# nRF24L01_SMD_402.net
KiCad netlist of a schematic drawn in EAGLE
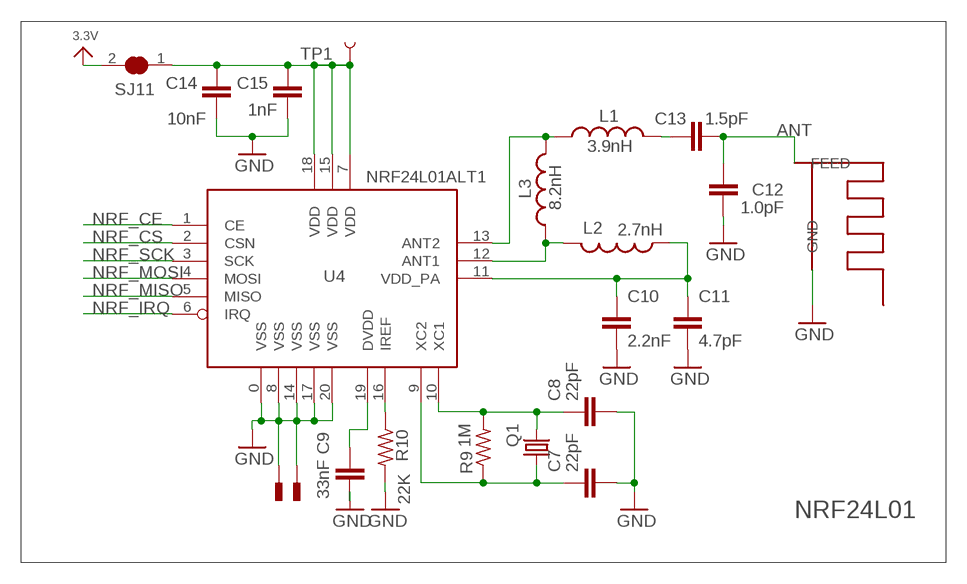
[diagram p0: schematic, sheet 1]

(export (version "E")
  (design (tool "Eeschema 10.0.6"))
  (components
    (comp (ref "ANT2")
      (value "NRF24L01_ANTENNA")
      (footprint "eagle-import:NRF24L01_ANT")
      (libsource (lib "eagle-import") (part "NRF24L01_ANTENNA"))
    )
    (comp (ref "C7")
      (value "22pF")
      (footprint "eagle-import:C0402")
      (libsource (lib "eagle-import") (part "C-EUC0402"))
    )
    (comp (ref "C8")
      (value "22pF")
      (footprint "eagle-import:C0402")
      (libsource (lib "eagle-import") (part "C-EUC0402"))
    )
    (comp (ref "C9")
      (value "33nF")
      (footprint "eagle-import:C0402")
      (libsource (lib "eagle-import") (part "C-EUC0402"))
    )
    (comp (ref "C10")
      (value "2.2nF")
      (footprint "eagle-import:C0402")
      (libsource (lib "eagle-import") (part "C-EUC0402"))
    )
    (comp (ref "C11")
      (value "4.7pF")
      (footprint "eagle-import:C0402")
      (libsource (lib "eagle-import") (part "C-EUC0402"))
    )
    (comp (ref "C12")
      (value "1.0pF")
      (footprint "eagle-import:C0402")
      (libsource (lib "eagle-import") (part "C-EUC0402"))
    )
    (comp (ref "C13")
      (value "1.5pF")
      (footprint "eagle-import:C0402")
      (libsource (lib "eagle-import") (part "C-EUC0402"))
    )
    (comp (ref "C14")
      (value "10nF")
      (footprint "eagle-import:C0402")
      (libsource (lib "eagle-import") (part "C-EUC0402"))
    )
    (comp (ref "C15")
      (value "1nF")
      (footprint "eagle-import:C0402")
      (libsource (lib "eagle-import") (part "C-EUC0402"))
    )
    (comp (ref "L1")
      (value "3.9nH")
      (footprint "eagle-import:L0402")
      (libsource (lib "eagle-import") (part "L-USL0402"))
    )
    (comp (ref "L2")
      (value "2.7nH")
      (footprint "eagle-import:L0402")
      (libsource (lib "eagle-import") (part "L-USL0402"))
    )
    (comp (ref "L3")
      (value "8.2nH")
      (footprint "eagle-import:L0402")
      (libsource (lib "eagle-import") (part "L-USL0402"))
    )
    (comp (ref "Q1")
      (value "KX-7")
      (footprint "eagle-import:3.2X2.5_KX-7")
      (libsource (lib "eagle-import") (part "KX-7"))
    )
    (comp (ref "R9")
      (value "1M")
      (footprint "eagle-import:R0402")
      (libsource (lib "eagle-import") (part "R-US_R0402"))
    )
    (comp (ref "R10")
      (value "22K")
      (footprint "eagle-import:R0402")
      (libsource (lib "eagle-import") (part "R-US_R0402"))
    )
    (comp (ref "SJ11")
      (value "SOLDERJUMPER_CLOSED")
      (footprint "eagle-import:SOLDERJUMPER_CLOSEDWIRE")
      (libsource (lib "eagle-import") (part "SOLDERJUMPER_CLOSED"))
    )
    (comp (ref "TP1")
      (value "TEST-POINT3X5")
      (footprint "eagle-import:PAD.03X.05")
      (libsource (lib "eagle-import") (part "TEST-POINT3X5"))
    )
    (comp (ref "U$27")
      (value "PAD")
      (footprint "eagle-import:PAD-0.008")
      (libsource (lib "eagle-import") (part "PAD"))
    )
    (comp (ref "U$28")
      (value "PAD")
      (footprint "eagle-import:PAD-0.008")
      (libsource (lib "eagle-import") (part "PAD"))
    )
    (comp (ref "U4")
      (value "NRF24L01ALT1")
      (footprint "eagle-import:QFN20_ALT1")
      (libsource (lib "eagle-import") (part "NRF24L01ALT1"))
    )
  )
  (nets
    (net (code "1") (name "/ANT") (class "Default")
      (node (ref "ANT2") (pin "FEED") (pinfunction "FEED_FEED") (pintype "bidirectional"))
      (node (ref "C12") (pin "2") (pinfunction "2_2") (pintype "passive"))
      (node (ref "C13") (pin "2") (pinfunction "2_2") (pintype "passive"))
    )
    (net (code "2") (name "/NRF_CE") (class "Default")
      (node (ref "U4") (pin "1") (pinfunction "CE_1") (pintype "input"))
    )
    (net (code "3") (name "/NRF_CS") (class "Default")
      (node (ref "U4") (pin "2") (pinfunction "CSN_2") (pintype "input"))
    )
    (net (code "4") (name "/NRF_IRQ") (class "Default")
      (node (ref "U4") (pin "6") (pinfunction "IRQ_6") (pintype "output"))
    )
    (net (code "5") (name "/NRF_MISO") (class "Default")
      (node (ref "U4") (pin "5") (pinfunction "MISO_5") (pintype "output"))
    )
    (net (code "6") (name "/NRF_MOSI") (class "Default")
      (node (ref "U4") (pin "4") (pinfunction "MOSI_4") (pintype "input"))
    )
    (net (code "7") (name "/NRF_SCK") (class "Default")
      (node (ref "U4") (pin "3") (pinfunction "SCK_3") (pintype "input"))
    )
    (net (code "8") (name "3.3V") (class "Default")
      (node (ref "SJ11") (pin "2") (pinfunction "2_2") (pintype "passive"))
    )
    (net (code "9") (name "GND") (class "Default")
      (node (ref "ANT2") (pin "GND") (pinfunction "GND_GND") (pintype "bidirectional"))
      (node (ref "C10") (pin "2") (pinfunction "2_2") (pintype "passive"))
      (node (ref "C11") (pin "2") (pinfunction "2_2") (pintype "passive"))
      (node (ref "C12") (pin "1") (pinfunction "1_1") (pintype "passive"))
      (node (ref "C14") (pin "1") (pinfunction "1_1") (pintype "passive"))
      (node (ref "C15") (pin "1") (pinfunction "1_1") (pintype "passive"))
      (node (ref "C7") (pin "2") (pinfunction "2_2") (pintype "passive"))
      (node (ref "C8") (pin "2") (pinfunction "2_2") (pintype "passive"))
      (node (ref "C9") (pin "2") (pinfunction "2_2") (pintype "passive"))
      (node (ref "R10") (pin "2") (pinfunction "2_2") (pintype "passive"))
      (node (ref "U$27") (pin "P$1") (pinfunction "P$1_P$1") (pintype "bidirectional"))
      (node (ref "U$28") (pin "P$1") (pinfunction "P$1_P$1") (pintype "bidirectional"))
      (node (ref "U4") (pin "0") (pinfunction "VSS_0") (pintype "power_in"))
      (node (ref "U4") (pin "14") (pinfunction "VSS_14") (pintype "power_in"))
      (node (ref "U4") (pin "17") (pinfunction "VSS_17") (pintype "power_in"))
      (node (ref "U4") (pin "20") (pinfunction "VSS_20") (pintype "power_in"))
      (node (ref "U4") (pin "8") (pinfunction "VSS_8") (pintype "power_in"))
    )
    (net (code "10") (name "Net-(C13-Pad1)") (class "Default")
      (node (ref "C13") (pin "1") (pinfunction "1_1") (pintype "passive"))
      (node (ref "L1") (pin "2") (pinfunction "2_2") (pintype "passive"))
    )
    (net (code "11") (name "Net-(Q1-2)") (class "Default")
      (node (ref "C8") (pin "1") (pinfunction "1_1") (pintype "passive"))
      (node (ref "Q1") (pin "3") (pinfunction "2_3") (pintype "passive"))
      (node (ref "R9") (pin "2") (pinfunction "2_2") (pintype "passive"))
      (node (ref "U4") (pin "10") (pinfunction "XC1_10") (pintype "input"))
    )
    (net (code "12") (name "Net-(TP1-1)") (class "Default")
      (node (ref "C14") (pin "2") (pinfunction "2_2") (pintype "passive"))
      (node (ref "C15") (pin "2") (pinfunction "2_2") (pintype "passive"))
      (node (ref "SJ11") (pin "1") (pinfunction "1_1") (pintype "passive"))
      (node (ref "TP1") (pin "P$1") (pinfunction "1_P$1") (pintype "bidirectional"))
      (node (ref "U4") (pin "15") (pinfunction "VDD_15") (pintype "power_in"))
      (node (ref "U4") (pin "18") (pinfunction "VDD_18") (pintype "power_in"))
      (node (ref "U4") (pin "7") (pinfunction "VDD_7") (pintype "power_in"))
    )
    (net (code "13") (name "Net-(U4-ANT1)") (class "Default")
      (node (ref "L2") (pin "2") (pinfunction "2_2") (pintype "passive"))
      (node (ref "L3") (pin "1") (pinfunction "1_1") (pintype "passive"))
      (node (ref "U4") (pin "12") (pinfunction "ANT1_12") (pintype "output"))
    )
    (net (code "14") (name "Net-(U4-ANT2)") (class "Default")
      (node (ref "L1") (pin "1") (pinfunction "1_1") (pintype "passive"))
      (node (ref "L3") (pin "2") (pinfunction "2_2") (pintype "passive"))
      (node (ref "U4") (pin "13") (pinfunction "ANT2_13") (pintype "output"))
    )
    (net (code "15") (name "Net-(U4-DVDD)") (class "Default")
      (node (ref "C9") (pin "1") (pinfunction "1_1") (pintype "passive"))
      (node (ref "U4") (pin "19") (pinfunction "DVDD_19") (pintype "power_in"))
    )
    (net (code "16") (name "Net-(U4-IREF)") (class "Default")
      (node (ref "R10") (pin "1") (pinfunction "1_1") (pintype "passive"))
      (node (ref "U4") (pin "16") (pinfunction "IREF_16") (pintype "input"))
    )
    (net (code "17") (name "Net-(U4-VDD_PA)") (class "Default")
      (node (ref "C10") (pin "1") (pinfunction "1_1") (pintype "passive"))
      (node (ref "C11") (pin "1") (pinfunction "1_1") (pintype "passive"))
      (node (ref "L2") (pin "1") (pinfunction "1_1") (pintype "passive"))
      (node (ref "U4") (pin "11") (pinfunction "VDD_PA_11") (pintype "power_in"))
    )
    (net (code "18") (name "Net-(U4-XC2)") (class "Default")
      (node (ref "C7") (pin "1") (pinfunction "1_1") (pintype "passive"))
      (node (ref "Q1") (pin "1") (pinfunction "1_1") (pintype "passive"))
      (node (ref "R9") (pin "1") (pinfunction "1_1") (pintype "passive"))
      (node (ref "U4") (pin "9") (pinfunction "XC2_9") (pintype "input"))
    )
  )
)
